# DMX-Card.net
KiCad netlist of a schematic drawn in EAGLE
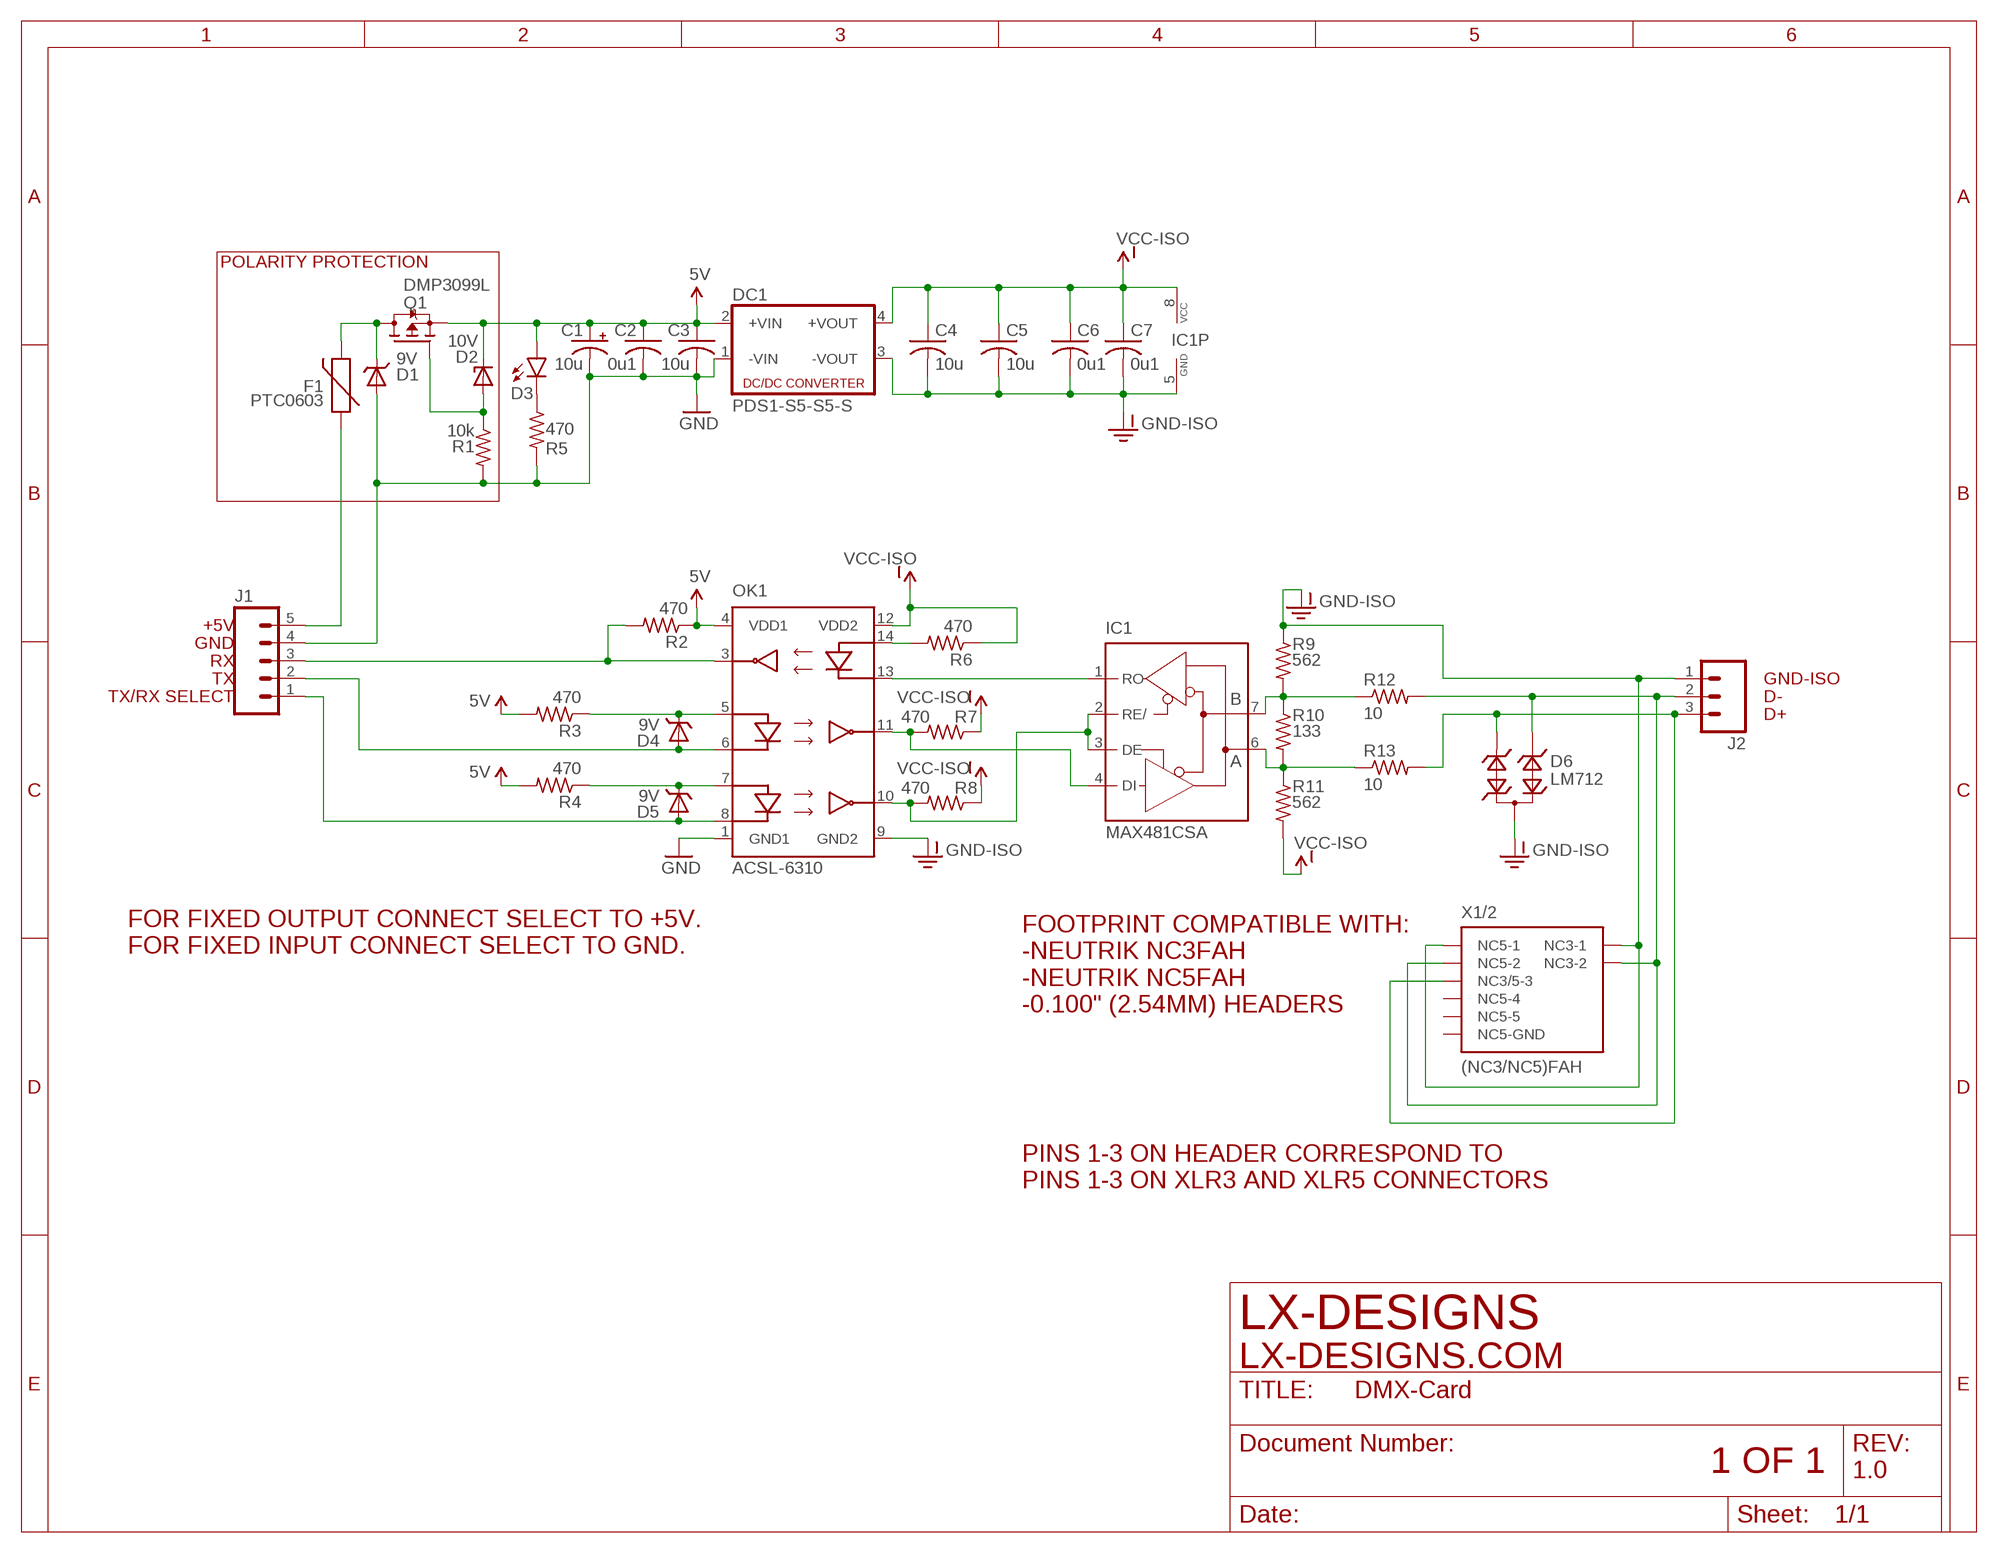
[diagram p0: schematic, sheet 1]

(export (version "E")
  (design (tool "Eeschema 10.0.6"))
  (components
    (comp (ref "C1")
      (value "10u")
      (footprint "eagle-import:E2,5-5-NOSILK")
      (libsource (lib "eagle-import") (part "CPOL-USE2.5-5-NOSILK"))
    )
    (comp (ref "C2")
      (value "0u1")
      (footprint "eagle-import:C0603K")
      (libsource (lib "eagle-import") (part "C-USC0603K"))
    )
    (comp (ref "C3")
      (value "10u")
      (footprint "eagle-import:C0603K")
      (libsource (lib "eagle-import") (part "C-USC0603K"))
    )
    (comp (ref "C4")
      (value "10u")
      (footprint "eagle-import:C0603K")
      (libsource (lib "eagle-import") (part "C-USC0603K"))
    )
    (comp (ref "C5")
      (value "10u")
      (footprint "eagle-import:C0603K")
      (libsource (lib "eagle-import") (part "C-USC0603K"))
    )
    (comp (ref "C6")
      (value "0u1")
      (footprint "eagle-import:C0603K")
      (libsource (lib "eagle-import") (part "C-USC0603K"))
    )
    (comp (ref "C7")
      (value "0u1")
      (footprint "eagle-import:C0603K")
      (libsource (lib "eagle-import") (part "C-USC0603K"))
    )
    (comp (ref "D1")
      (value "9V")
      (footprint "eagle-import:SOD323-NOSILK")
      (libsource (lib "eagle-import") (part "TVS-DIODESOD323-NOSILK"))
    )
    (comp (ref "D2")
      (value "10V")
      (footprint "eagle-import:SOD323")
      (libsource (lib "eagle-import") (part "ZENER-DIODESOD-323"))
    )
    (comp (ref "D3")
      (value "LED0603")
      (footprint "eagle-import:LED-0603")
      (libsource (lib "eagle-import") (part "LED0603"))
    )
    (comp (ref "D4")
      (value "9V")
      (footprint "eagle-import:SOD323-NOSILK")
      (libsource (lib "eagle-import") (part "TVS-DIODESOD323-NOSILK"))
    )
    (comp (ref "D5")
      (value "9V")
      (footprint "eagle-import:SOD323-NOSILK")
      (libsource (lib "eagle-import") (part "TVS-DIODESOD323-NOSILK"))
    )
    (comp (ref "D6")
      (value "LM712")
      (footprint "eagle-import:SOT23")
      (libsource (lib "eagle-import") (part "CDSOT23-SM712SOT23-STANDARD"))
    )
    (comp (ref "DC1")
      (value "PDS1-S5-S5-S")
      (footprint "eagle-import:4SIL")
      (libsource (lib "eagle-import") (part "VA-?S0505"))
    )
    (comp (ref "F1")
      (value "PTC0603")
      (footprint "eagle-import:0603")
      (libsource (lib "eagle-import") (part "PTC0603"))
    )
    (comp (ref "IC1")
      (value "MAX481CSA")
      (footprint "eagle-import:SO08")
      (fields (field (name "MF") "MAXIM"))
      (libsource (lib "eagle-import") (part "MAX481CSA"))
    )
    (comp (ref "J1")
      (value "M05NO_SILK")
      (footprint "eagle-import:1X05_NO_SILK")
      (libsource (lib "eagle-import") (part "M05NO_SILK"))
    )
    (comp (ref "J2")
      (value "M031X03_NO_SILK")
      (footprint "eagle-import:1X03_NO_SILK")
      (libsource (lib "eagle-import") (part "M031X03_NO_SILK"))
    )
    (comp (ref "OK1")
      (value "ACSL-6310")
      (footprint "eagle-import:SO-16")
      (libsource (lib "eagle-import") (part "ACSL-60"))
    )
    (comp (ref "Q1")
      (value "DMP3099L")
      (footprint "eagle-import:SOT23")
      (libsource (lib "eagle-import") (part "BSA223SPSOT23"))
    )
    (comp (ref "R1")
      (value "10k")
      (footprint "eagle-import:R0603")
      (libsource (lib "eagle-import") (part "R-US_R0603"))
    )
    (comp (ref "R2")
      (value "470")
      (footprint "eagle-import:R0603")
      (libsource (lib "eagle-import") (part "R-US_R0603"))
    )
    (comp (ref "R3")
      (value "470")
      (footprint "eagle-import:R0603")
      (libsource (lib "eagle-import") (part "R-US_R0603"))
    )
    (comp (ref "R4")
      (value "470")
      (footprint "eagle-import:R0603")
      (libsource (lib "eagle-import") (part "R-US_R0603"))
    )
    (comp (ref "R5")
      (value "470")
      (footprint "eagle-import:R0603")
      (libsource (lib "eagle-import") (part "R-US_R0603"))
    )
    (comp (ref "R6")
      (value "470")
      (footprint "eagle-import:R0603")
      (libsource (lib "eagle-import") (part "R-US_R0603"))
    )
    (comp (ref "R7")
      (value "470")
      (footprint "eagle-import:R0603")
      (libsource (lib "eagle-import") (part "R-US_R0603"))
    )
    (comp (ref "R8")
      (value "470")
      (footprint "eagle-import:R0603")
      (libsource (lib "eagle-import") (part "R-US_R0603"))
    )
    (comp (ref "R9")
      (value "562")
      (footprint "eagle-import:R0603")
      (libsource (lib "eagle-import") (part "R-US_R0603"))
    )
    (comp (ref "R10")
      (value "133")
      (footprint "eagle-import:R0603")
      (libsource (lib "eagle-import") (part "R-US_R0603"))
    )
    (comp (ref "R11")
      (value "562")
      (footprint "eagle-import:R0603")
      (libsource (lib "eagle-import") (part "R-US_R0603"))
    )
    (comp (ref "R12")
      (value "10")
      (footprint "eagle-import:R0603")
      (libsource (lib "eagle-import") (part "R-US_R0603"))
    )
    (comp (ref "R13")
      (value "10")
      (footprint "eagle-import:R0603")
      (libsource (lib "eagle-import") (part "R-US_R0603"))
    )
    (comp (ref "X1/2")
      (value "(NC3/NC5)FAH")
      (footprint "eagle-import:NC3FAH-NC5FAH-NOSILK")
      (libsource (lib "eagle-import") (part "CUSTOMNC3FAH-NC3MAH-NOSILK"))
    )
  )
  (nets
    (net (code "1") (name "5V") (class "Default")
      (node (ref "C1") (pin "+") (pinfunction "+_+") (pintype "passive"))
      (node (ref "C2") (pin "1") (pinfunction "1_1") (pintype "passive"))
      (node (ref "C3") (pin "1") (pinfunction "1_1") (pintype "passive"))
      (node (ref "D2") (pin "C") (pinfunction "C_C") (pintype "passive"))
      (node (ref "D3") (pin "A") (pinfunction "A_A") (pintype "passive"))
      (node (ref "DC1") (pin "2") (pinfunction "+VIN_2") (pintype "passive"))
      (node (ref "OK1") (pin "4") (pinfunction "VDD1_4") (pintype "power_in"))
      (node (ref "Q1") (pin "2") (pinfunction "S_2") (pintype "passive"))
      (node (ref "R2") (pin "1") (pinfunction "1_1") (pintype "passive"))
      (node (ref "R3") (pin "2") (pinfunction "2_2") (pintype "passive"))
      (node (ref "R4") (pin "2") (pinfunction "2_2") (pintype "passive"))
    )
    (net (code "2") (name "GND") (class "Default")
      (node (ref "C1") (pin "-") (pinfunction "-_-") (pintype "passive"))
      (node (ref "C2") (pin "2") (pinfunction "2_2") (pintype "passive"))
      (node (ref "C3") (pin "2") (pinfunction "2_2") (pintype "passive"))
      (node (ref "D1") (pin "A") (pinfunction "A_A") (pintype "passive"))
      (node (ref "DC1") (pin "1") (pinfunction "-VIN_1") (pintype "passive"))
      (node (ref "J1") (pin "4") (pinfunction "4_4") (pintype "passive"))
      (node (ref "OK1") (pin "1") (pinfunction "GND1_1") (pintype "bidirectional"))
      (node (ref "R1") (pin "2") (pinfunction "2_2") (pintype "passive"))
      (node (ref "R5") (pin "2") (pinfunction "2_2") (pintype "passive"))
    )
    (net (code "3") (name "GND-ISO") (class "Default")
      (node (ref "C4") (pin "2") (pinfunction "2_2") (pintype "passive"))
      (node (ref "C5") (pin "2") (pinfunction "2_2") (pintype "passive"))
      (node (ref "C6") (pin "2") (pinfunction "2_2") (pintype "passive"))
      (node (ref "C7") (pin "2") (pinfunction "2_2") (pintype "passive"))
      (node (ref "D6") (pin "3") (pinfunction "3_3") (pintype "passive"))
      (node (ref "DC1") (pin "3") (pinfunction "-VOUT_3") (pintype "passive"))
      (node (ref "IC1") (pin "5") (pinfunction "GND_5") (pintype "power_in"))
      (node (ref "J2") (pin "1") (pinfunction "1_1") (pintype "passive"))
      (node (ref "OK1") (pin "9") (pinfunction "GND2_9") (pintype "power_in"))
      (node (ref "R9") (pin "1") (pinfunction "1_1") (pintype "passive"))
      (node (ref "X1/2") (pin "NC3-1") (pinfunction "NC3-1_NC3-1") (pintype "bidirectional"))
      (node (ref "X1/2") (pin "NC5-1") (pinfunction "NC5-1_NC5-1") (pintype "bidirectional"))
    )
    (net (code "4") (name "Net-(D3-PadC)") (class "Default")
      (node (ref "D3") (pin "C") (pinfunction "C_C") (pintype "passive"))
      (node (ref "R5") (pin "1") (pinfunction "1_1") (pintype "passive"))
    )
    (net (code "5") (name "Net-(D6-Pad1)") (class "Default")
      (node (ref "D6") (pin "1") (pinfunction "1_1") (pintype "passive"))
      (node (ref "J2") (pin "2") (pinfunction "2_2") (pintype "passive"))
      (node (ref "R12") (pin "2") (pinfunction "2_2") (pintype "passive"))
      (node (ref "X1/2") (pin "NC3-2") (pinfunction "NC3-2_NC3-2") (pintype "bidirectional"))
      (node (ref "X1/2") (pin "NC5-2") (pinfunction "NC5-2_NC5-2") (pintype "bidirectional"))
    )
    (net (code "6") (name "Net-(F1-Pad1)") (class "Default")
      (node (ref "F1") (pin "1") (pinfunction "1_1") (pintype "bidirectional"))
      (node (ref "J1") (pin "5") (pinfunction "5_5") (pintype "passive"))
    )
    (net (code "7") (name "Net-(IC1A-A)") (class "Default")
      (node (ref "IC1") (pin "6") (pinfunction "A_6") (pintype "passive"))
      (node (ref "R10") (pin "2") (pinfunction "2_2") (pintype "passive"))
      (node (ref "R11") (pin "1") (pinfunction "1_1") (pintype "passive"))
      (node (ref "R13") (pin "1") (pinfunction "1_1") (pintype "passive"))
    )
    (net (code "8") (name "Net-(IC1A-B)") (class "Default")
      (node (ref "IC1") (pin "7") (pinfunction "B_7") (pintype "passive"))
      (node (ref "R10") (pin "1") (pinfunction "1_1") (pintype "passive"))
      (node (ref "R12") (pin "1") (pinfunction "1_1") (pintype "passive"))
      (node (ref "R9") (pin "2") (pinfunction "2_2") (pintype "passive"))
    )
    (net (code "9") (name "Net-(IC1A-DE)") (class "Default")
      (node (ref "IC1") (pin "2") (pinfunction "RE/_2") (pintype "input"))
      (node (ref "IC1") (pin "3") (pinfunction "DE_3") (pintype "input"))
      (node (ref "OK1") (pin "10") (pinfunction "VO2_10") (pintype "output"))
      (node (ref "R8") (pin "2") (pinfunction "2_2") (pintype "passive"))
    )
    (net (code "10") (name "Net-(IC1A-DI)") (class "Default")
      (node (ref "IC1") (pin "4") (pinfunction "DI_4") (pintype "input"))
      (node (ref "OK1") (pin "11") (pinfunction "VO1_11") (pintype "output"))
      (node (ref "R7") (pin "2") (pinfunction "2_2") (pintype "passive"))
    )
    (net (code "11") (name "Net-(IC1A-RO)") (class "Default")
      (node (ref "IC1") (pin "1") (pinfunction "RO_1") (pintype "output"))
      (node (ref "OK1") (pin "13") (pinfunction "C3_13") (pintype "output"))
    )
    (net (code "12") (name "Net-(OK1-A1)") (class "Default")
      (node (ref "D4") (pin "C") (pinfunction "C_C") (pintype "passive"))
      (node (ref "OK1") (pin "5") (pinfunction "A1_5") (pintype "input"))
      (node (ref "R3") (pin "1") (pinfunction "1_1") (pintype "passive"))
    )
    (net (code "13") (name "Net-(OK1-A2)") (class "Default")
      (node (ref "D5") (pin "C") (pinfunction "C_C") (pintype "passive"))
      (node (ref "OK1") (pin "7") (pinfunction "A2_7") (pintype "input"))
      (node (ref "R4") (pin "1") (pinfunction "1_1") (pintype "passive"))
    )
    (net (code "14") (name "Net-(OK1-A3)") (class "Default")
      (node (ref "OK1") (pin "14") (pinfunction "A3_14") (pintype "input"))
      (node (ref "R6") (pin "2") (pinfunction "2_2") (pintype "passive"))
    )
    (net (code "15") (name "Net-(OK1-C1)") (class "Default")
      (node (ref "D4") (pin "A") (pinfunction "A_A") (pintype "passive"))
      (node (ref "J1") (pin "2") (pinfunction "2_2") (pintype "passive"))
      (node (ref "OK1") (pin "6") (pinfunction "C1_6") (pintype "output"))
    )
    (net (code "16") (name "Net-(OK1-C2)") (class "Default")
      (node (ref "D5") (pin "A") (pinfunction "A_A") (pintype "passive"))
      (node (ref "J1") (pin "1") (pinfunction "1_1") (pintype "passive"))
      (node (ref "OK1") (pin "8") (pinfunction "C2_8") (pintype "output"))
    )
    (net (code "17") (name "Net-(OK1-V03)") (class "Default")
      (node (ref "J1") (pin "3") (pinfunction "3_3") (pintype "passive"))
      (node (ref "OK1") (pin "3") (pinfunction "V03_3") (pintype "output"))
      (node (ref "R2") (pin "2") (pinfunction "2_2") (pintype "passive"))
    )
    (net (code "18") (name "Net-(Q1-D)") (class "Default")
      (node (ref "D1") (pin "C") (pinfunction "C_C") (pintype "passive"))
      (node (ref "F1") (pin "2") (pinfunction "2_2") (pintype "bidirectional"))
      (node (ref "Q1") (pin "3") (pinfunction "D_3") (pintype "passive"))
    )
    (net (code "19") (name "Net-(Q1-G)") (class "Default")
      (node (ref "D2") (pin "A") (pinfunction "A_A") (pintype "passive"))
      (node (ref "Q1") (pin "1") (pinfunction "G_1") (pintype "passive"))
      (node (ref "R1") (pin "1") (pinfunction "1_1") (pintype "passive"))
    )
    (net (code "20") (name "Net-(X1/2-NC3{slash}5-3)") (class "Default")
      (node (ref "D6") (pin "2") (pinfunction "2_2") (pintype "passive"))
      (node (ref "J2") (pin "3") (pinfunction "3_3") (pintype "passive"))
      (node (ref "R13") (pin "2") (pinfunction "2_2") (pintype "passive"))
      (node (ref "X1/2") (pin "NC3-3") (pinfunction "NC3/5-3_NC3-3") (pintype "bidirectional"))
    )
    (net (code "21") (name "VCC-ISO") (class "Default")
      (node (ref "C4") (pin "1") (pinfunction "1_1") (pintype "passive"))
      (node (ref "C5") (pin "1") (pinfunction "1_1") (pintype "passive"))
      (node (ref "C6") (pin "1") (pinfunction "1_1") (pintype "passive"))
      (node (ref "C7") (pin "1") (pinfunction "1_1") (pintype "passive"))
      (node (ref "DC1") (pin "4") (pinfunction "+VOUT_4") (pintype "passive"))
      (node (ref "IC1") (pin "8") (pinfunction "VCC_8") (pintype "power_in"))
      (node (ref "OK1") (pin "12") (pinfunction "VDD2_12") (pintype "power_in"))
      (node (ref "R11") (pin "2") (pinfunction "2_2") (pintype "passive"))
      (node (ref "R6") (pin "1") (pinfunction "1_1") (pintype "passive"))
      (node (ref "R7") (pin "1") (pinfunction "1_1") (pintype "passive"))
      (node (ref "R8") (pin "1") (pinfunction "1_1") (pintype "passive"))
    )
    (net (code "22") (name "unconnected-(X1/2-NC5-GND-PadGND)") (class "Default")
      (node (ref "X1/2") (pin "GND") (pinfunction "NC5-GND_GND") (pintype "bidirectional"))
    )
    (net (code "23") (name "unconnected-(X1/2-PadNC5-4)") (class "Default")
      (node (ref "X1/2") (pin "NC5-4") (pinfunction "NC5-4_NC5-4") (pintype "bidirectional"))
    )
    (net (code "24") (name "unconnected-(X1/2-PadNC5-5)") (class "Default")
      (node (ref "X1/2") (pin "NC5-5") (pinfunction "NC5-5_NC5-5") (pintype "bidirectional"))
    )
  )
)
